# Sheet1.net
KiCad netlist of a schematic drawn in Altium Designer
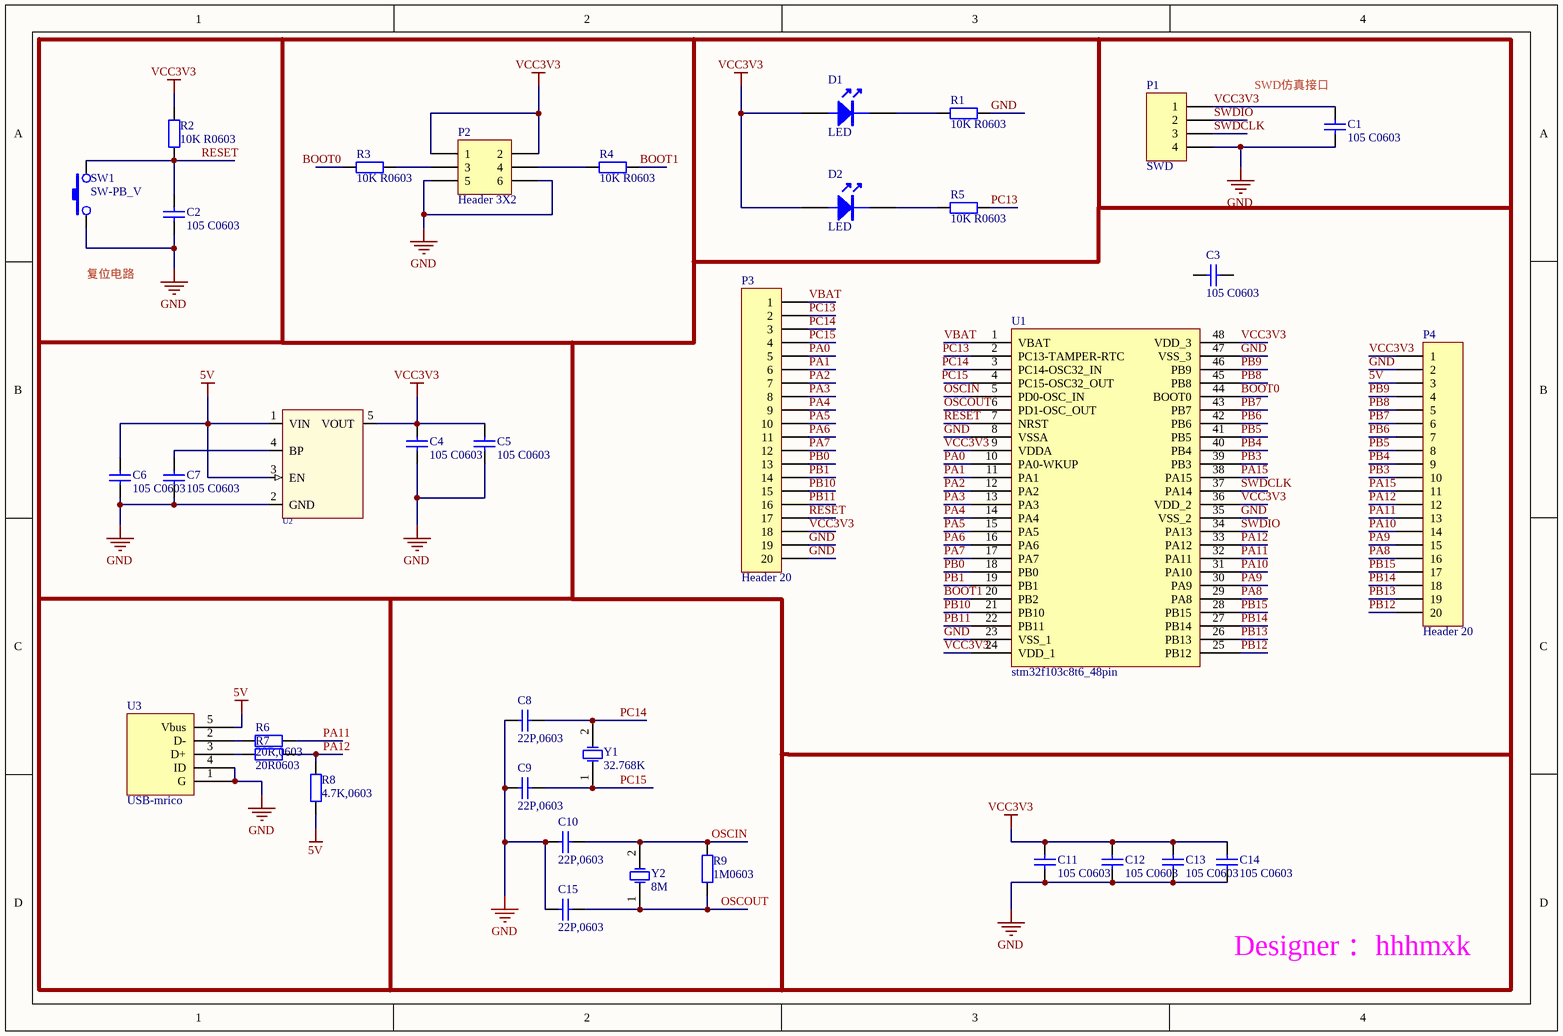
[diagram p0: Sheet1.SchDoc]

(export (version "E")
  (design (tool "Eeschema 10.0.6"))
  (components
    (comp (ref "C1")
      (value "105 C0603")
      (footprint "C 0603")
      (fields (field (name "PUBLISHER") "Altium Limited"))
      (libsource (lib "stm32原理图库") (part "Cap"))
    )
    (comp (ref "C2")
      (value "105 C0603")
      (footprint "C 0603")
      (fields (field (name "PUBLISHER") "Altium Limited"))
      (libsource (lib "stm32原理图库") (part "Cap"))
    )
    (comp (ref "C3")
      (value "105 C0603")
      (footprint "C 0603")
      (fields (field (name "PUBLISHER") "Altium Limited"))
      (libsource (lib "stm32原理图库") (part "Cap"))
    )
    (comp (ref "C4")
      (value "105 C0603")
      (footprint "C 0603")
      (fields (field (name "PUBLISHER") "Altium Limited"))
      (libsource (lib "stm32原理图库") (part "Cap"))
    )
    (comp (ref "C5")
      (value "105 C0603")
      (footprint "C 0603")
      (fields (field (name "PUBLISHER") "Altium Limited"))
      (libsource (lib "stm32原理图库") (part "Cap"))
    )
    (comp (ref "C6")
      (value "105 C0603")
      (footprint "C 0603")
      (fields (field (name "PUBLISHER") "Altium Limited"))
      (libsource (lib "stm32原理图库") (part "Cap"))
    )
    (comp (ref "C7")
      (value "105 C0603")
      (footprint "C 0603")
      (fields (field (name "PUBLISHER") "Altium Limited"))
      (libsource (lib "stm32原理图库") (part "Cap"))
    )
    (comp (ref "C8")
      (value "22P,0603")
      (footprint "C 0603")
      (description "Capacitor")
      (fields (field (name "PUBLISHER") "Altium Limited"))
      (libsource (lib "STM32F103C8T6") (part "Cap"))
    )
    (comp (ref "C9")
      (value "22P,0603")
      (footprint "C 0603")
      (description "Capacitor")
      (fields (field (name "PUBLISHER") "Altium Limited"))
      (libsource (lib "STM32F103C8T6") (part "Cap"))
    )
    (comp (ref "C10")
      (value "22P,0603")
      (footprint "C 0603")
      (description "Capacitor")
      (fields (field (name "PUBLISHER") "Altium Limited"))
      (libsource (lib "STM32F103C8T6") (part "Cap"))
    )
    (comp (ref "C11")
      (value "105 C0603")
      (footprint "C 0603")
      (fields (field (name "PUBLISHER") "Altium Limited"))
      (libsource (lib "stm32原理图库") (part "Cap"))
    )
    (comp (ref "C12")
      (value "105 C0603")
      (footprint "C 0603")
      (fields (field (name "PUBLISHER") "Altium Limited"))
      (libsource (lib "stm32原理图库") (part "Cap"))
    )
    (comp (ref "C13")
      (value "105 C0603")
      (footprint "C 0603")
      (fields (field (name "PUBLISHER") "Altium Limited"))
      (libsource (lib "stm32原理图库") (part "Cap"))
    )
    (comp (ref "C14")
      (value "105 C0603")
      (footprint "C 0603")
      (fields (field (name "PUBLISHER") "Altium Limited"))
      (libsource (lib "stm32原理图库") (part "Cap"))
    )
    (comp (ref "C15")
      (value "22P,0603")
      (footprint "C 0603")
      (description "Capacitor")
      (fields (field (name "PUBLISHER") "Altium Limited"))
      (libsource (lib "STM32F103C8T6") (part "Cap"))
    )
    (comp (ref "D1") (value "LED") (footprint "LED 0805G") (libsource (lib "stm32原理图库") (part "LED")))
    (comp (ref "D2") (value "LED") (footprint "LED 0805G") (libsource (lib "stm32原理图库") (part "LED")))
    (comp (ref "P1")
      (value "SWD")
      (footprint "HDR-1X4_H")
      (description "Header, 4-Pin")
      (fields (field (name "PUBLISHER") "Altium Limited"))
      (libsource (lib "stm32原理图库") (part "Header 4"))
    )
    (comp (ref "P2")
      (value "Header 3X2")
      (footprint "HDR-3X2")
      (description "Header, 3-Pin, Dual row")
      (fields (field (name "PUBLISHER") "Altium Limited"))
      (libsource (lib "stm32原理图库") (part "Header 3X2"))
    )
    (comp (ref "P3")
      (value "Header 20")
      (footprint "HDR1X20")
      (description "Header, 20-Pin")
      (fields (field (name "PUBLISHER") "Altium Limited"))
      (libsource (lib "") (part "Header 20_1"))
    )
    (comp (ref "P4")
      (value "Header 20")
      (footprint "HDR1X20")
      (description "Header, 20-Pin")
      (fields (field (name "PUBLISHER") "Altium Limited"))
      (libsource (lib "stm32原理图库") (part "Header 20"))
    )
    (comp (ref "R1")
      (value "10K R0603")
      (footprint "R 0603")
      (fields (field (name "PUBLISHER") "Altium Limited"))
      (libsource (lib "stm32原理图库") (part "Res2"))
    )
    (comp (ref "R2")
      (value "10K R0603")
      (footprint "R 0603")
      (fields (field (name "PUBLISHER") "Altium Limited"))
      (libsource (lib "") (part "Res2_1"))
    )
    (comp (ref "R3")
      (value "10K R0603")
      (footprint "R 0603")
      (fields (field (name "PUBLISHER") "Altium Limited"))
      (libsource (lib "stm32原理图库") (part "Res2"))
    )
    (comp (ref "R4")
      (value "10K R0603")
      (footprint "R 0603")
      (fields (field (name "PUBLISHER") "Altium Limited"))
      (libsource (lib "stm32原理图库") (part "Res2"))
    )
    (comp (ref "R5")
      (value "10K R0603")
      (footprint "R 0603")
      (fields (field (name "PUBLISHER") "Altium Limited"))
      (libsource (lib "stm32原理图库") (part "Res2"))
    )
    (comp (ref "R6")
      (value "20R,0603")
      (footprint "R 0603")
      (description "Resistor")
      (fields (field (name "PUBLISHER") "Altium Limited"))
      (libsource (lib "") (part "Res2_1"))
    )
    (comp (ref "R7")
      (value "20R0603")
      (footprint "R 0603")
      (description "Resistor")
      (fields (field (name "PUBLISHER") "Altium Limited"))
      (libsource (lib "") (part "Res2_1"))
    )
    (comp (ref "R8")
      (value "4.7K,0603")
      (footprint "R 0603")
      (description "Resistor")
      (fields (field (name "PUBLISHER") "Altium Limited"))
      (libsource (lib "STM32F103C8T6") (part "Res2"))
    )
    (comp (ref "R9")
      (value "1M0603")
      (footprint "R 0603")
      (description "Resistor")
      (fields (field (name "PUBLISHER") "Altium Limited"))
      (libsource (lib "STM32F103C8T6") (part "Res2"))
    )
    (comp (ref "SW1")
      (value "SW-PB_V")
      (footprint "TSW SMD-3*6*2.5")
      (libsource (lib "stm32原理图库") (part "SW-PB_V"))
    )
    (comp (ref "U1")
      (value "stm32f103c8t6_48pin")
      (footprint "TQFP48 7x7_L")
      (libsource (lib "STM32_Schlib") (part "stm32f103c8t6_48pin"))
    )
    (comp (ref "U2")
      (value "RT9193")
      (footprint "SOT23-5L")
      (fields (field (name "ICA_PARTNUM") "$$2191094$$RT9193-15CU5") (field (name "PART NUMBER") "TMP-13"))
      (libsource (lib "stm32原理图库") (part "RT9193X_5P"))
    )
    (comp (ref "U3")
      (value "USB-mrico")
      (footprint "USB-micro_B")
      (libsource (lib "STM32F103C8T6") (part "usb-STM"))
    )
    (comp (ref "Y1")
      (value "32.768K")
      (footprint "XTAL-49S DIP")
      (description "Crystal Oscillator")
      (fields (field (name "PUBLISHER") "Altium Limited"))
      (libsource (lib "STM32F103C8T6") (part "XTAL"))
    )
    (comp (ref "Y2")
      (value "8M")
      (footprint "XTAL-49S DIP")
      (description "Crystal Oscillator")
      (fields (field (name "PUBLISHER") "Altium Limited"))
      (libsource (lib "STM32F103C8T6") (part "XTAL"))
    )
  )
  (nets
    (net (code "1") (name "/BOOT0") (class "Default")
      (node (ref "R3") (pin "1") (pinfunction "1_1") (pintype "passive"))
      (node (ref "U1") (pin "44") (pinfunction "BOOT0_44") (pintype "passive"))
    )
    (net (code "2") (name "/BOOT1") (class "Default")
      (node (ref "R4") (pin "2") (pinfunction "2_2") (pintype "passive"))
      (node (ref "U1") (pin "20") (pinfunction "PB2_20") (pintype "passive"))
    )
    (net (code "3") (name "/OSCIN") (class "Default")
      (node (ref "C10") (pin "1") (pinfunction "1_1") (pintype "passive"))
      (node (ref "R9") (pin "2") (pinfunction "2_2") (pintype "passive"))
      (node (ref "U1") (pin "5") (pinfunction "PD0-OSC_IN_5") (pintype "passive"))
      (node (ref "Y2") (pin "2") (pinfunction "OSC2_2") (pintype "passive"))
    )
    (net (code "4") (name "/OSCOUT") (class "Default")
      (node (ref "C15") (pin "1") (pinfunction "1_1") (pintype "passive"))
      (node (ref "R9") (pin "1") (pinfunction "1_1") (pintype "passive"))
      (node (ref "U1") (pin "6") (pinfunction "PD1-OSC_OUT_6") (pintype "passive"))
      (node (ref "Y2") (pin "1") (pinfunction "OSC1_1") (pintype "passive"))
    )
    (net (code "5") (name "/PA0") (class "Default")
      (node (ref "P3") (pin "5") (pinfunction "5_5") (pintype "passive"))
      (node (ref "U1") (pin "10") (pinfunction "PA0-WKUP_10") (pintype "passive"))
    )
    (net (code "6") (name "/PA1") (class "Default")
      (node (ref "P3") (pin "6") (pinfunction "6_6") (pintype "passive"))
      (node (ref "U1") (pin "11") (pinfunction "PA1_11") (pintype "passive"))
    )
    (net (code "7") (name "/PA2") (class "Default")
      (node (ref "P3") (pin "7") (pinfunction "7_7") (pintype "passive"))
      (node (ref "U1") (pin "12") (pinfunction "PA2_12") (pintype "passive"))
    )
    (net (code "8") (name "/PA3") (class "Default")
      (node (ref "P3") (pin "8") (pinfunction "8_8") (pintype "passive"))
      (node (ref "U1") (pin "13") (pinfunction "PA3_13") (pintype "passive"))
    )
    (net (code "9") (name "/PA4") (class "Default")
      (node (ref "P3") (pin "9") (pinfunction "9_9") (pintype "passive"))
      (node (ref "U1") (pin "14") (pinfunction "PA4_14") (pintype "passive"))
    )
    (net (code "10") (name "/PA5") (class "Default")
      (node (ref "P3") (pin "10") (pinfunction "10_10") (pintype "passive"))
      (node (ref "U1") (pin "15") (pinfunction "PA5_15") (pintype "passive"))
    )
    (net (code "11") (name "/PA6") (class "Default")
      (node (ref "P3") (pin "11") (pinfunction "11_11") (pintype "passive"))
      (node (ref "U1") (pin "16") (pinfunction "PA6_16") (pintype "passive"))
    )
    (net (code "12") (name "/PA7") (class "Default")
      (node (ref "P3") (pin "12") (pinfunction "12_12") (pintype "passive"))
      (node (ref "U1") (pin "17") (pinfunction "PA7_17") (pintype "passive"))
    )
    (net (code "13") (name "/PA8") (class "Default")
      (node (ref "P4") (pin "16") (pinfunction "16_16") (pintype "passive"))
      (node (ref "U1") (pin "29") (pinfunction "PA8_29") (pintype "passive"))
    )
    (net (code "14") (name "/PA9") (class "Default")
      (node (ref "P4") (pin "15") (pinfunction "15_15") (pintype "passive"))
      (node (ref "U1") (pin "30") (pinfunction "PA9_30") (pintype "passive"))
    )
    (net (code "15") (name "/PA10") (class "Default")
      (node (ref "P4") (pin "14") (pinfunction "14_14") (pintype "passive"))
      (node (ref "U1") (pin "31") (pinfunction "PA10_31") (pintype "passive"))
    )
    (net (code "16") (name "/PA11") (class "Default")
      (node (ref "P4") (pin "13") (pinfunction "13_13") (pintype "passive"))
      (node (ref "R6") (pin "2") (pinfunction "2_2") (pintype "passive"))
      (node (ref "U1") (pin "32") (pinfunction "PA11_32") (pintype "passive"))
    )
    (net (code "17") (name "/PA12") (class "Default")
      (node (ref "P4") (pin "12") (pinfunction "12_12") (pintype "passive"))
      (node (ref "R7") (pin "2") (pinfunction "2_2") (pintype "passive"))
      (node (ref "R8") (pin "2") (pinfunction "2_2") (pintype "passive"))
      (node (ref "U1") (pin "33") (pinfunction "PA12_33") (pintype "passive"))
    )
    (net (code "18") (name "/PA15") (class "Default")
      (node (ref "P4") (pin "11") (pinfunction "11_11") (pintype "passive"))
      (node (ref "U1") (pin "38") (pinfunction "PA15_38") (pintype "passive"))
    )
    (net (code "19") (name "/PB0") (class "Default")
      (node (ref "P3") (pin "13") (pinfunction "13_13") (pintype "passive"))
      (node (ref "U1") (pin "18") (pinfunction "PB0_18") (pintype "passive"))
    )
    (net (code "20") (name "/PB1") (class "Default")
      (node (ref "P3") (pin "14") (pinfunction "14_14") (pintype "passive"))
      (node (ref "U1") (pin "19") (pinfunction "PB1_19") (pintype "passive"))
    )
    (net (code "21") (name "/PB3") (class "Default")
      (node (ref "P4") (pin "10") (pinfunction "10_10") (pintype "passive"))
      (node (ref "U1") (pin "39") (pinfunction "PB3_39") (pintype "passive"))
    )
    (net (code "22") (name "/PB4") (class "Default")
      (node (ref "P4") (pin "9") (pinfunction "9_9") (pintype "passive"))
      (node (ref "U1") (pin "40") (pinfunction "PB4_40") (pintype "passive"))
    )
    (net (code "23") (name "/PB5") (class "Default")
      (node (ref "P4") (pin "8") (pinfunction "8_8") (pintype "passive"))
      (node (ref "U1") (pin "41") (pinfunction "PB5_41") (pintype "passive"))
    )
    (net (code "24") (name "/PB6") (class "Default")
      (node (ref "P4") (pin "7") (pinfunction "7_7") (pintype "passive"))
      (node (ref "U1") (pin "42") (pinfunction "PB6_42") (pintype "passive"))
    )
    (net (code "25") (name "/PB7") (class "Default")
      (node (ref "P4") (pin "6") (pinfunction "6_6") (pintype "passive"))
      (node (ref "U1") (pin "43") (pinfunction "PB7_43") (pintype "passive"))
    )
    (net (code "26") (name "/PB8") (class "Default")
      (node (ref "P4") (pin "5") (pinfunction "5_5") (pintype "passive"))
      (node (ref "U1") (pin "45") (pinfunction "PB8_45") (pintype "passive"))
    )
    (net (code "27") (name "/PB9") (class "Default")
      (node (ref "P4") (pin "4") (pinfunction "4_4") (pintype "passive"))
      (node (ref "U1") (pin "46") (pinfunction "PB9_46") (pintype "passive"))
    )
    (net (code "28") (name "/PB10") (class "Default")
      (node (ref "P3") (pin "15") (pinfunction "15_15") (pintype "passive"))
      (node (ref "U1") (pin "21") (pinfunction "PB10_21") (pintype "passive"))
    )
    (net (code "29") (name "/PB11") (class "Default")
      (node (ref "P3") (pin "16") (pinfunction "16_16") (pintype "passive"))
      (node (ref "U1") (pin "22") (pinfunction "PB11_22") (pintype "passive"))
    )
    (net (code "30") (name "/PB12") (class "Default")
      (node (ref "P4") (pin "20") (pinfunction "20_20") (pintype "passive"))
      (node (ref "U1") (pin "25") (pinfunction "PB12_25") (pintype "passive"))
    )
    (net (code "31") (name "/PB13") (class "Default")
      (node (ref "P4") (pin "19") (pinfunction "19_19") (pintype "passive"))
      (node (ref "U1") (pin "26") (pinfunction "PB13_26") (pintype "passive"))
    )
    (net (code "32") (name "/PB14") (class "Default")
      (node (ref "P4") (pin "18") (pinfunction "18_18") (pintype "passive"))
      (node (ref "U1") (pin "27") (pinfunction "PB14_27") (pintype "passive"))
    )
    (net (code "33") (name "/PB15") (class "Default")
      (node (ref "P4") (pin "17") (pinfunction "17_17") (pintype "passive"))
      (node (ref "U1") (pin "28") (pinfunction "PB15_28") (pintype "passive"))
    )
    (net (code "34") (name "/PC13") (class "Default")
      (node (ref "P3") (pin "2") (pinfunction "2_2") (pintype "passive"))
      (node (ref "R5") (pin "2") (pinfunction "2_2") (pintype "passive"))
      (node (ref "U1") (pin "2") (pinfunction "PC13-TAMPER-RTC_2") (pintype "passive"))
    )
    (net (code "35") (name "/PC14") (class "Default")
      (node (ref "C8") (pin "1") (pinfunction "1_1") (pintype "passive"))
      (node (ref "P3") (pin "3") (pinfunction "3_3") (pintype "passive"))
      (node (ref "U1") (pin "3") (pinfunction "PC14-OSC32_IN_3") (pintype "passive"))
      (node (ref "Y1") (pin "2") (pinfunction "OSC2_2") (pintype "passive"))
    )
    (net (code "36") (name "/PC15") (class "Default")
      (node (ref "C9") (pin "1") (pinfunction "1_1") (pintype "passive"))
      (node (ref "P3") (pin "4") (pinfunction "4_4") (pintype "passive"))
      (node (ref "U1") (pin "4") (pinfunction "PC15-OSC32_OUT_4") (pintype "passive"))
      (node (ref "Y1") (pin "1") (pinfunction "OSC1_1") (pintype "passive"))
    )
    (net (code "37") (name "/RESET") (class "Default")
      (node (ref "C2") (pin "2") (pinfunction "2_2") (pintype "passive"))
      (node (ref "P3") (pin "17") (pinfunction "17_17") (pintype "passive"))
      (node (ref "R2") (pin "1") (pinfunction "1_1") (pintype "passive"))
      (node (ref "SW1") (pin "2") (pinfunction "2_2") (pintype "passive"))
      (node (ref "U1") (pin "7") (pinfunction "NRST_7") (pintype "passive"))
    )
    (net (code "38") (name "/SWDCLK") (class "Default")
      (node (ref "P1") (pin "3") (pinfunction "3_3") (pintype "passive"))
      (node (ref "U1") (pin "37") (pinfunction "PA14_37") (pintype "passive"))
    )
    (net (code "39") (name "/SWDIO") (class "Default")
      (node (ref "P1") (pin "2") (pinfunction "2_2") (pintype "passive"))
      (node (ref "U1") (pin "34") (pinfunction "PA13_34") (pintype "passive"))
    )
    (net (code "40") (name "/VBAT") (class "Default")
      (node (ref "P3") (pin "1") (pinfunction "1_1") (pintype "passive"))
      (node (ref "U1") (pin "1") (pinfunction "VBAT_1") (pintype "passive"))
    )
    (net (code "41") (name "5V") (class "Default")
      (node (ref "C6") (pin "2") (pinfunction "2_2") (pintype "passive"))
      (node (ref "P4") (pin "3") (pinfunction "3_3") (pintype "passive"))
      (node (ref "R8") (pin "1") (pinfunction "1_1") (pintype "passive"))
      (node (ref "U2") (pin "1") (pinfunction "VIN_1") (pintype "power_in"))
      (node (ref "U2") (pin "3") (pinfunction "EN_3") (pintype "input"))
      (node (ref "U3") (pin "5") (pinfunction "Vbus_5") (pintype "passive"))
    )
    (net (code "42") (name "GND") (class "Default")
      (node (ref "C1") (pin "1") (pinfunction "1_1") (pintype "passive"))
      (node (ref "C10") (pin "2") (pinfunction "2_2") (pintype "passive"))
      (node (ref "C11") (pin "1") (pinfunction "1_1") (pintype "passive"))
      (node (ref "C12") (pin "1") (pinfunction "1_1") (pintype "passive"))
      (node (ref "C13") (pin "1") (pinfunction "1_1") (pintype "passive"))
      (node (ref "C14") (pin "1") (pinfunction "1_1") (pintype "passive"))
      (node (ref "C15") (pin "2") (pinfunction "2_2") (pintype "passive"))
      (node (ref "C2") (pin "1") (pinfunction "1_1") (pintype "passive"))
      (node (ref "C4") (pin "1") (pinfunction "1_1") (pintype "passive"))
      (node (ref "C5") (pin "1") (pinfunction "1_1") (pintype "passive"))
      (node (ref "C6") (pin "1") (pinfunction "1_1") (pintype "passive"))
      (node (ref "C7") (pin "1") (pinfunction "1_1") (pintype "passive"))
      (node (ref "C8") (pin "2") (pinfunction "2_2") (pintype "passive"))
      (node (ref "C9") (pin "2") (pinfunction "2_2") (pintype "passive"))
      (node (ref "P1") (pin "4") (pinfunction "4_4") (pintype "passive"))
      (node (ref "P2") (pin "5") (pinfunction "5_5") (pintype "passive"))
      (node (ref "P2") (pin "6") (pinfunction "6_6") (pintype "passive"))
      (node (ref "P3") (pin "19") (pinfunction "19_19") (pintype "passive"))
      (node (ref "P3") (pin "20") (pinfunction "20_20") (pintype "passive"))
      (node (ref "P4") (pin "2") (pinfunction "2_2") (pintype "passive"))
      (node (ref "R1") (pin "2") (pinfunction "2_2") (pintype "passive"))
      (node (ref "SW1") (pin "1") (pinfunction "1_1") (pintype "passive"))
      (node (ref "U1") (pin "23") (pinfunction "VSS_1_23") (pintype "passive"))
      (node (ref "U1") (pin "35") (pinfunction "VSS_2_35") (pintype "passive"))
      (node (ref "U1") (pin "47") (pinfunction "VSS_3_47") (pintype "passive"))
      (node (ref "U1") (pin "8") (pinfunction "VSSA_8") (pintype "passive"))
      (node (ref "U2") (pin "2") (pinfunction "GND_2") (pintype "power_in"))
      (node (ref "U3") (pin "1") (pinfunction "G_1") (pintype "passive"))
      (node (ref "U3") (pin "4") (pinfunction "ID_4") (pintype "passive"))
    )
    (net (code "43") (name "Net-(D1-Pad2)") (class "Default")
      (node (ref "D1") (pin "2") (pinfunction "2_2") (pintype "passive"))
      (node (ref "R1") (pin "1") (pinfunction "1_1") (pintype "passive"))
    )
    (net (code "44") (name "Net-(D2-Pad2)") (class "Default")
      (node (ref "D2") (pin "2") (pinfunction "2_2") (pintype "passive"))
      (node (ref "R5") (pin "1") (pinfunction "1_1") (pintype "passive"))
    )
    (net (code "45") (name "Net-(P2-Pad3)") (class "Default")
      (node (ref "P2") (pin "3") (pinfunction "3_3") (pintype "passive"))
      (node (ref "R3") (pin "2") (pinfunction "2_2") (pintype "passive"))
    )
    (net (code "46") (name "Net-(P2-Pad4)") (class "Default")
      (node (ref "P2") (pin "4") (pinfunction "4_4") (pintype "passive"))
      (node (ref "R4") (pin "1") (pinfunction "1_1") (pintype "passive"))
    )
    (net (code "47") (name "Net-(U2-BP)") (class "Default")
      (node (ref "C7") (pin "2") (pinfunction "2_2") (pintype "passive"))
      (node (ref "U2") (pin "4") (pinfunction "BP_4") (pintype "passive"))
    )
    (net (code "48") (name "Net-(U3-D+)") (class "Default")
      (node (ref "R7") (pin "1") (pinfunction "1_1") (pintype "passive"))
      (node (ref "U3") (pin "3") (pinfunction "D+_3") (pintype "passive"))
    )
    (net (code "49") (name "Net-(U3-D-)") (class "Default")
      (node (ref "R6") (pin "1") (pinfunction "1_1") (pintype "passive"))
      (node (ref "U3") (pin "2") (pinfunction "D-_2") (pintype "passive"))
    )
    (net (code "50") (name "VCC3V3") (class "Default")
      (node (ref "C1") (pin "2") (pinfunction "2_2") (pintype "passive"))
      (node (ref "C11") (pin "2") (pinfunction "2_2") (pintype "passive"))
      (node (ref "C12") (pin "2") (pinfunction "2_2") (pintype "passive"))
      (node (ref "C13") (pin "2") (pinfunction "2_2") (pintype "passive"))
      (node (ref "C14") (pin "2") (pinfunction "2_2") (pintype "passive"))
      (node (ref "C4") (pin "2") (pinfunction "2_2") (pintype "passive"))
      (node (ref "C5") (pin "2") (pinfunction "2_2") (pintype "passive"))
      (node (ref "D1") (pin "1") (pinfunction "1_1") (pintype "passive"))
      (node (ref "D2") (pin "1") (pinfunction "1_1") (pintype "passive"))
      (node (ref "P1") (pin "1") (pinfunction "1_1") (pintype "passive"))
      (node (ref "P2") (pin "1") (pinfunction "1_1") (pintype "passive"))
      (node (ref "P2") (pin "2") (pinfunction "2_2") (pintype "passive"))
      (node (ref "P3") (pin "18") (pinfunction "18_18") (pintype "passive"))
      (node (ref "P4") (pin "1") (pinfunction "1_1") (pintype "passive"))
      (node (ref "R2") (pin "2") (pinfunction "2_2") (pintype "passive"))
      (node (ref "U1") (pin "24") (pinfunction "VDD_1_24") (pintype "passive"))
      (node (ref "U1") (pin "36") (pinfunction "VDD_2_36") (pintype "passive"))
      (node (ref "U1") (pin "48") (pinfunction "VDD_3_48") (pintype "passive"))
      (node (ref "U1") (pin "9") (pinfunction "VDDA_9") (pintype "passive"))
      (node (ref "U2") (pin "5") (pinfunction "VOUT_5") (pintype "power_in"))
    )
    (net (code "51") (name "unconnected-(C3-Pad1)") (class "Default")
      (node (ref "C3") (pin "1") (pinfunction "1_1") (pintype "passive"))
    )
    (net (code "52") (name "unconnected-(C3-Pad2)") (class "Default")
      (node (ref "C3") (pin "2") (pinfunction "2_2") (pintype "passive"))
    )
  )
)
